# SparkFun_Differential_I2C_Breakout_PCA96.net
KiCad netlist of a schematic drawn in EAGLE
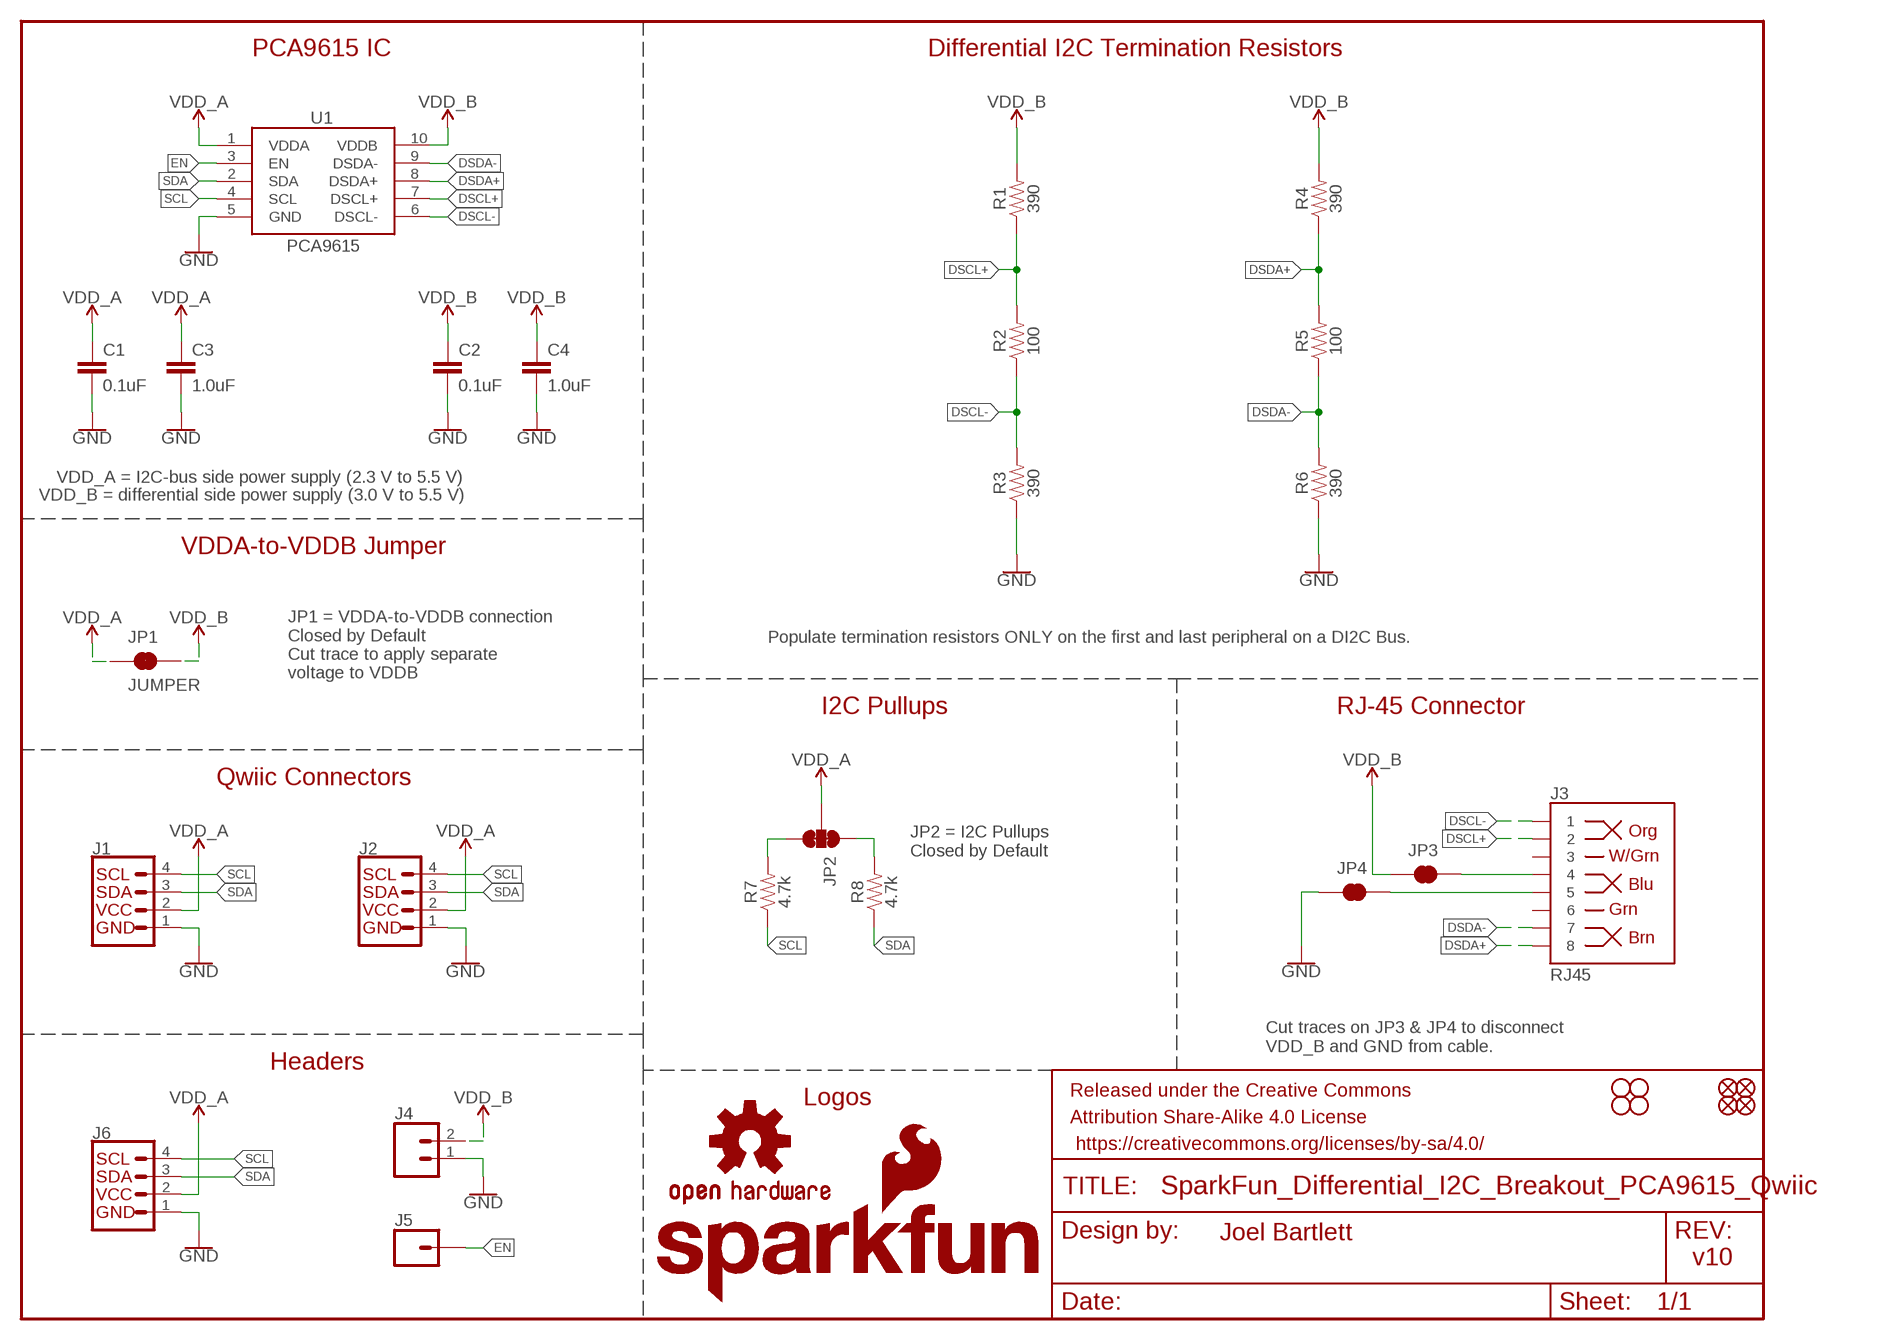
[diagram p0: schematic, sheet 1]

(export (version "E")
  (design (tool "Eeschema 10.0.6"))
  (components
    (comp (ref "C1")
      (value "0.1uF")
      (footprint "eagle-import:0603")
      (libsource (lib "eagle-import") (part "0.1UF-0603-25V-(+80/-20%)"))
    )
    (comp (ref "C2")
      (value "0.1uF")
      (footprint "eagle-import:0603")
      (libsource (lib "eagle-import") (part "0.1UF-0603-25V-(+80/-20%)"))
    )
    (comp (ref "C3")
      (value "1.0uF")
      (footprint "eagle-import:0603")
      (libsource (lib "eagle-import") (part "1.0UF-0603-16V-10%"))
    )
    (comp (ref "C4")
      (value "1.0uF")
      (footprint "eagle-import:0603")
      (libsource (lib "eagle-import") (part "1.0UF-0603-16V-10%"))
    )
    (comp (ref "FD1")
      (value "FIDUCIALUFIDUCIAL")
      (footprint "eagle-import:FIDUCIAL-MICRO")
      (libsource (lib "eagle-import") (part "FIDUCIALUFIDUCIAL"))
    )
    (comp (ref "FD2")
      (value "FIDUCIALUFIDUCIAL")
      (footprint "eagle-import:FIDUCIAL-MICRO")
      (libsource (lib "eagle-import") (part "FIDUCIALUFIDUCIAL"))
    )
    (comp (ref "FD3")
      (value "FIDUCIALUFIDUCIAL")
      (footprint "eagle-import:FIDUCIAL-MICRO")
      (libsource (lib "eagle-import") (part "FIDUCIALUFIDUCIAL"))
    )
    (comp (ref "FD4")
      (value "FIDUCIALUFIDUCIAL")
      (footprint "eagle-import:FIDUCIAL-MICRO")
      (libsource (lib "eagle-import") (part "FIDUCIALUFIDUCIAL"))
    )
    (comp (ref "FRAME1")
      (value "FRAME-LETTER")
      (footprint "eagle-import:CREATIVE_COMMONS")
      (libsource (lib "eagle-import") (part "FRAME-LETTER"))
    )
    (comp (ref "H1")
      (value "STAND-OFF")
      (footprint "eagle-import:STAND-OFF")
      (libsource (lib "eagle-import") (part "STAND-OFF"))
    )
    (comp (ref "H2")
      (value "STAND-OFF")
      (footprint "eagle-import:STAND-OFF")
      (libsource (lib "eagle-import") (part "STAND-OFF"))
    )
    (comp (ref "H3")
      (value "STAND-OFF")
      (footprint "eagle-import:STAND-OFF")
      (libsource (lib "eagle-import") (part "STAND-OFF"))
    )
    (comp (ref "H4")
      (value "STAND-OFF")
      (footprint "eagle-import:STAND-OFF")
      (libsource (lib "eagle-import") (part "STAND-OFF"))
    )
    (comp (ref "J1")
      (value "QWIIC_CONNECTORJS-1MM")
      (footprint "eagle-import:1X04_1MM_RA")
      (libsource (lib "eagle-import") (part "QWIIC_CONNECTORJS-1MM"))
    )
    (comp (ref "J2")
      (value "QWIIC_CONNECTORJS-1MM")
      (footprint "eagle-import:1X04_1MM_RA")
      (libsource (lib "eagle-import") (part "QWIIC_CONNECTORJS-1MM"))
    )
    (comp (ref "J3")
      (value "RJ45")
      (footprint "eagle-import:RJ45-8")
      (libsource (lib "eagle-import") (part "RJ45-8"))
    )
    (comp (ref "J4")
      (value "CONN_021X02_NO_SILK")
      (footprint "eagle-import:1X02_NO_SILK")
      (libsource (lib "eagle-import") (part "CONN_021X02_NO_SILK"))
    )
    (comp (ref "J5")
      (value "CONN_01PTH_NO_SILK_YES_STOP")
      (footprint "eagle-import:1X01_NO_SILK")
      (libsource (lib "eagle-import") (part "CONN_01PTH_NO_SILK_YES_STOP"))
    )
    (comp (ref "J6")
      (value "I2C_STANDARD_NO_SILK")
      (footprint "eagle-import:1X04_NO_SILK")
      (libsource (lib "eagle-import") (part "I2C_STANDARD_NO_SILK"))
    )
    (comp (ref "JP1")
      (value "JUMPER")
      (footprint "eagle-import:SMT-JUMPER_2_NC_TRACE_SILK")
      (libsource (lib "eagle-import") (part "JUMPER-SMT_2_NC_TRACE_SILK"))
    )
    (comp (ref "JP2")
      (value "JUMPER-SMT_3_2-NC_TRACE_SILK")
      (footprint "eagle-import:SMT-JUMPER_3_2-NC_TRACE_SILK")
      (libsource (lib "eagle-import") (part "JUMPER-SMT_3_2-NC_TRACE_SILK"))
    )
    (comp (ref "JP3")
      (value "JUMPER-SMT_2_NC_TRACE_SILK")
      (footprint "eagle-import:SMT-JUMPER_2_NC_TRACE_SILK")
      (libsource (lib "eagle-import") (part "JUMPER-SMT_2_NC_TRACE_SILK"))
    )
    (comp (ref "JP4")
      (value "JUMPER-SMT_2_NC_TRACE_SILK")
      (footprint "eagle-import:SMT-JUMPER_2_NC_TRACE_SILK")
      (libsource (lib "eagle-import") (part "JUMPER-SMT_2_NC_TRACE_SILK"))
    )
    (comp (ref "LOGO1")
      (value "OSHW-LOGOM")
      (footprint "eagle-import:OSHW-LOGO-M")
      (libsource (lib "eagle-import") (part "OSHW-LOGOM"))
    )
    (comp (ref "LOGO5")
      (value "SFE_LOGO_NAME_FLAME.1_INCH")
      (footprint "eagle-import:SFE_LOGO_NAME_FLAME_.1")
      (libsource (lib "eagle-import") (part "SFE_LOGO_NAME_FLAME.1_INCH"))
    )
    (comp (ref "R1")
      (value "390")
      (footprint "eagle-import:0603")
      (libsource (lib "eagle-import") (part "390OHM-0603-1/10W-1%"))
    )
    (comp (ref "R2")
      (value "100")
      (footprint "eagle-import:0603")
      (libsource (lib "eagle-import") (part "100OHM-0603-1/10W-1%"))
    )
    (comp (ref "R3")
      (value "390")
      (footprint "eagle-import:0603")
      (libsource (lib "eagle-import") (part "390OHM-0603-1/10W-1%"))
    )
    (comp (ref "R4")
      (value "390")
      (footprint "eagle-import:0603")
      (libsource (lib "eagle-import") (part "390OHM-0603-1/10W-1%"))
    )
    (comp (ref "R5")
      (value "100")
      (footprint "eagle-import:0603")
      (libsource (lib "eagle-import") (part "100OHM-0603-1/10W-1%"))
    )
    (comp (ref "R6")
      (value "390")
      (footprint "eagle-import:0603")
      (libsource (lib "eagle-import") (part "390OHM-0603-1/10W-1%"))
    )
    (comp (ref "R7")
      (value "4.7k")
      (footprint "eagle-import:0603")
      (libsource (lib "eagle-import") (part "4.7KOHM-0603-1/10W-1%"))
    )
    (comp (ref "R8")
      (value "4.7k")
      (footprint "eagle-import:0603")
      (libsource (lib "eagle-import") (part "4.7KOHM-0603-1/10W-1%"))
    )
    (comp (ref "U1")
      (value "PCA9615")
      (footprint "eagle-import:TSSOP10")
      (libsource (lib "eagle-import") (part "PCA9615"))
    )
  )
  (nets
    (net (code "1") (name "DSCL+") (class "Default")
      (node (ref "J3") (pin "2") (pinfunction "2_2") (pintype "bidirectional"))
      (node (ref "R1") (pin "1") (pinfunction "1_1") (pintype "passive"))
      (node (ref "R2") (pin "2") (pinfunction "2_2") (pintype "passive"))
      (node (ref "U1") (pin "7") (pinfunction "DSCL+_7") (pintype "bidirectional"))
    )
    (net (code "2") (name "DSCL-") (class "Default")
      (node (ref "J3") (pin "1") (pinfunction "1_1") (pintype "bidirectional"))
      (node (ref "R2") (pin "1") (pinfunction "1_1") (pintype "passive"))
      (node (ref "R3") (pin "2") (pinfunction "2_2") (pintype "passive"))
      (node (ref "U1") (pin "6") (pinfunction "DSCL-_6") (pintype "bidirectional"))
    )
    (net (code "3") (name "DSDA+") (class "Default")
      (node (ref "J3") (pin "8") (pinfunction "8_8") (pintype "bidirectional"))
      (node (ref "R4") (pin "1") (pinfunction "1_1") (pintype "passive"))
      (node (ref "R5") (pin "2") (pinfunction "2_2") (pintype "passive"))
      (node (ref "U1") (pin "8") (pinfunction "DSDA+_8") (pintype "bidirectional"))
    )
    (net (code "4") (name "DSDA-") (class "Default")
      (node (ref "J3") (pin "7") (pinfunction "7_7") (pintype "bidirectional"))
      (node (ref "R5") (pin "1") (pinfunction "1_1") (pintype "passive"))
      (node (ref "R6") (pin "2") (pinfunction "2_2") (pintype "passive"))
      (node (ref "U1") (pin "9") (pinfunction "DSDA-_9") (pintype "bidirectional"))
    )
    (net (code "5") (name "EN") (class "Default")
      (node (ref "J5") (pin "1") (pinfunction "1_1") (pintype "passive"))
      (node (ref "U1") (pin "3") (pinfunction "EN_3") (pintype "bidirectional"))
    )
    (net (code "6") (name "GND") (class "Default")
      (node (ref "C1") (pin "2") (pinfunction "2_2") (pintype "passive"))
      (node (ref "C2") (pin "2") (pinfunction "2_2") (pintype "passive"))
      (node (ref "C3") (pin "2") (pinfunction "2_2") (pintype "passive"))
      (node (ref "C4") (pin "2") (pinfunction "2_2") (pintype "passive"))
      (node (ref "J1") (pin "1") (pinfunction "1_1") (pintype "power_in"))
      (node (ref "J2") (pin "1") (pinfunction "1_1") (pintype "power_in"))
      (node (ref "J4") (pin "1") (pinfunction "1_1") (pintype "passive"))
      (node (ref "J6") (pin "1") (pinfunction "GND_1") (pintype "power_in"))
      (node (ref "JP4") (pin "1") (pinfunction "1_1") (pintype "passive"))
      (node (ref "R3") (pin "1") (pinfunction "1_1") (pintype "passive"))
      (node (ref "R6") (pin "1") (pinfunction "1_1") (pintype "passive"))
      (node (ref "U1") (pin "5") (pinfunction "GND_5") (pintype "bidirectional"))
    )
    (net (code "7") (name "Net-(J3-Pad4)") (class "Default")
      (node (ref "J3") (pin "4") (pinfunction "4_4") (pintype "bidirectional"))
      (node (ref "JP3") (pin "2") (pinfunction "2_2") (pintype "passive"))
    )
    (net (code "8") (name "Net-(J3-Pad5)") (class "Default")
      (node (ref "J3") (pin "5") (pinfunction "5_5") (pintype "bidirectional"))
      (node (ref "JP4") (pin "2") (pinfunction "2_2") (pintype "passive"))
    )
    (net (code "9") (name "Net-(JP2-Pad1)") (class "Default")
      (node (ref "JP2") (pin "1") (pinfunction "1_1") (pintype "passive"))
      (node (ref "R8") (pin "2") (pinfunction "2_2") (pintype "passive"))
    )
    (net (code "10") (name "Net-(JP2-Pad3)") (class "Default")
      (node (ref "JP2") (pin "3") (pinfunction "3_3") (pintype "passive"))
      (node (ref "R7") (pin "2") (pinfunction "2_2") (pintype "passive"))
    )
    (net (code "11") (name "SCL") (class "Default")
      (node (ref "J1") (pin "4") (pinfunction "4_4") (pintype "passive"))
      (node (ref "J2") (pin "4") (pinfunction "4_4") (pintype "passive"))
      (node (ref "J6") (pin "4") (pinfunction "SCL_4") (pintype "passive"))
      (node (ref "R7") (pin "1") (pinfunction "1_1") (pintype "passive"))
      (node (ref "U1") (pin "4") (pinfunction "SCL_4") (pintype "bidirectional"))
    )
    (net (code "12") (name "SDA") (class "Default")
      (node (ref "J1") (pin "3") (pinfunction "3_3") (pintype "passive"))
      (node (ref "J2") (pin "3") (pinfunction "3_3") (pintype "passive"))
      (node (ref "J6") (pin "3") (pinfunction "SDA_3") (pintype "passive"))
      (node (ref "R8") (pin "1") (pinfunction "1_1") (pintype "passive"))
      (node (ref "U1") (pin "2") (pinfunction "SDA_2") (pintype "bidirectional"))
    )
    (net (code "13") (name "VDD_A") (class "Default")
      (node (ref "C1") (pin "1") (pinfunction "1_1") (pintype "passive"))
      (node (ref "C3") (pin "1") (pinfunction "1_1") (pintype "passive"))
      (node (ref "J1") (pin "2") (pinfunction "2_2") (pintype "power_in"))
      (node (ref "J2") (pin "2") (pinfunction "2_2") (pintype "power_in"))
      (node (ref "J6") (pin "2") (pinfunction "VCC_2") (pintype "power_in"))
      (node (ref "JP1") (pin "1") (pinfunction "1_1") (pintype "passive"))
      (node (ref "JP2") (pin "2") (pinfunction "2_2") (pintype "passive"))
      (node (ref "U1") (pin "1") (pinfunction "VDDA_1") (pintype "bidirectional"))
    )
    (net (code "14") (name "VDD_B") (class "Default")
      (node (ref "C2") (pin "1") (pinfunction "1_1") (pintype "passive"))
      (node (ref "C4") (pin "1") (pinfunction "1_1") (pintype "passive"))
      (node (ref "J4") (pin "2") (pinfunction "2_2") (pintype "passive"))
      (node (ref "JP1") (pin "2") (pinfunction "2_2") (pintype "passive"))
      (node (ref "JP3") (pin "1") (pinfunction "1_1") (pintype "passive"))
      (node (ref "R1") (pin "2") (pinfunction "2_2") (pintype "passive"))
      (node (ref "R4") (pin "2") (pinfunction "2_2") (pintype "passive"))
      (node (ref "U1") (pin "10") (pinfunction "VDDB_10") (pintype "bidirectional"))
    )
    (net (code "15") (name "unconnected-(J3-Pad3)") (class "Default")
      (node (ref "J3") (pin "3") (pinfunction "3_3") (pintype "bidirectional"))
    )
    (net (code "16") (name "unconnected-(J3-Pad6)") (class "Default")
      (node (ref "J3") (pin "6") (pinfunction "6_6") (pintype "bidirectional"))
    )
  )
)
